# Buzzer.net
KiCad netlist of a schematic drawn in Altium Designer
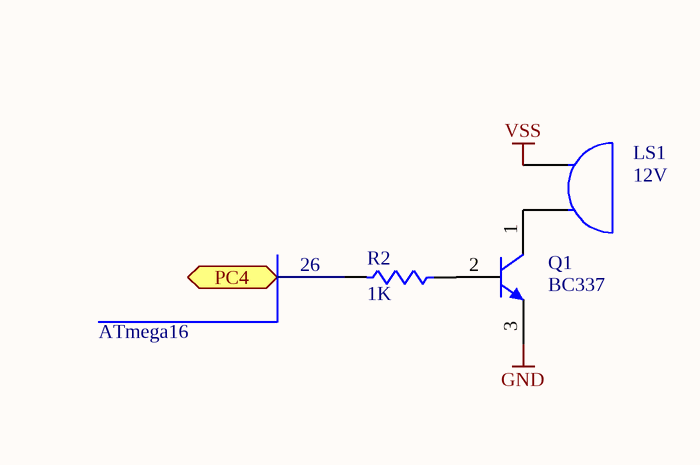
[diagram p0: Buzzer.SchDoc]

(export (version "E")
  (design (tool "Eeschema 10.0.6"))
  (components
    (comp (ref "LS1")
      (value "12V")
      (footprint "RB_7.62mm")
      (description "Sounder")
      (fields
        (field (name "MANUFACTURER") "Generic Components")
        (field (name "Comment") "Buzzer")
        (field (name "PUBLISHER") "Altium Limited")
      )
      (libsource (lib "my Libraries") (part "Buzzer"))
    )
    (comp (ref "Q1")
      (value "NPN")
      (footprint "TO92C")
      (description "Silicon Bipolar Transistor")
      (fields (field (name "DEVICE") "BC337"))
      (libsource (lib "my Libraries") (part "NPN"))
    )
    (comp (ref "R2")
      (value "1K")
      (footprint "AXIAL0.4")
      (description "Resistor")
      (fields (field (name "MANUFACTURER") "Generic Components") (field (name "PUBLISHER") "Altium Limited"))
      (libsource (lib "my Libraries") (part "Resistor"))
    )
  )
  (nets
    (net (code "1") (name "/PC4") (class "Default")
      (node (ref "R2") (pin "2") (pinfunction "2_2") (pintype "passive"))
    )
    (net (code "2") (name "GND") (class "Default")
      (node (ref "Q1") (pin "3") (pinfunction "E_3") (pintype "passive"))
    )
    (net (code "3") (name "Net-(LS1-B)") (class "Default")
      (node (ref "LS1") (pin "2") (pinfunction "B_2") (pintype "passive"))
      (node (ref "Q1") (pin "1") (pinfunction "C_1") (pintype "passive"))
    )
    (net (code "4") (name "Net-(Q1-B)") (class "Default")
      (node (ref "Q1") (pin "2") (pinfunction "B_2") (pintype "passive"))
      (node (ref "R2") (pin "1") (pinfunction "1_1") (pintype "passive"))
    )
    (net (code "5") (name "VSS") (class "Default")
      (node (ref "LS1") (pin "1") (pinfunction "A_1") (pintype "passive"))
    )
  )
)
